# LEDs.net
KiCad netlist of a schematic drawn in EAGLE
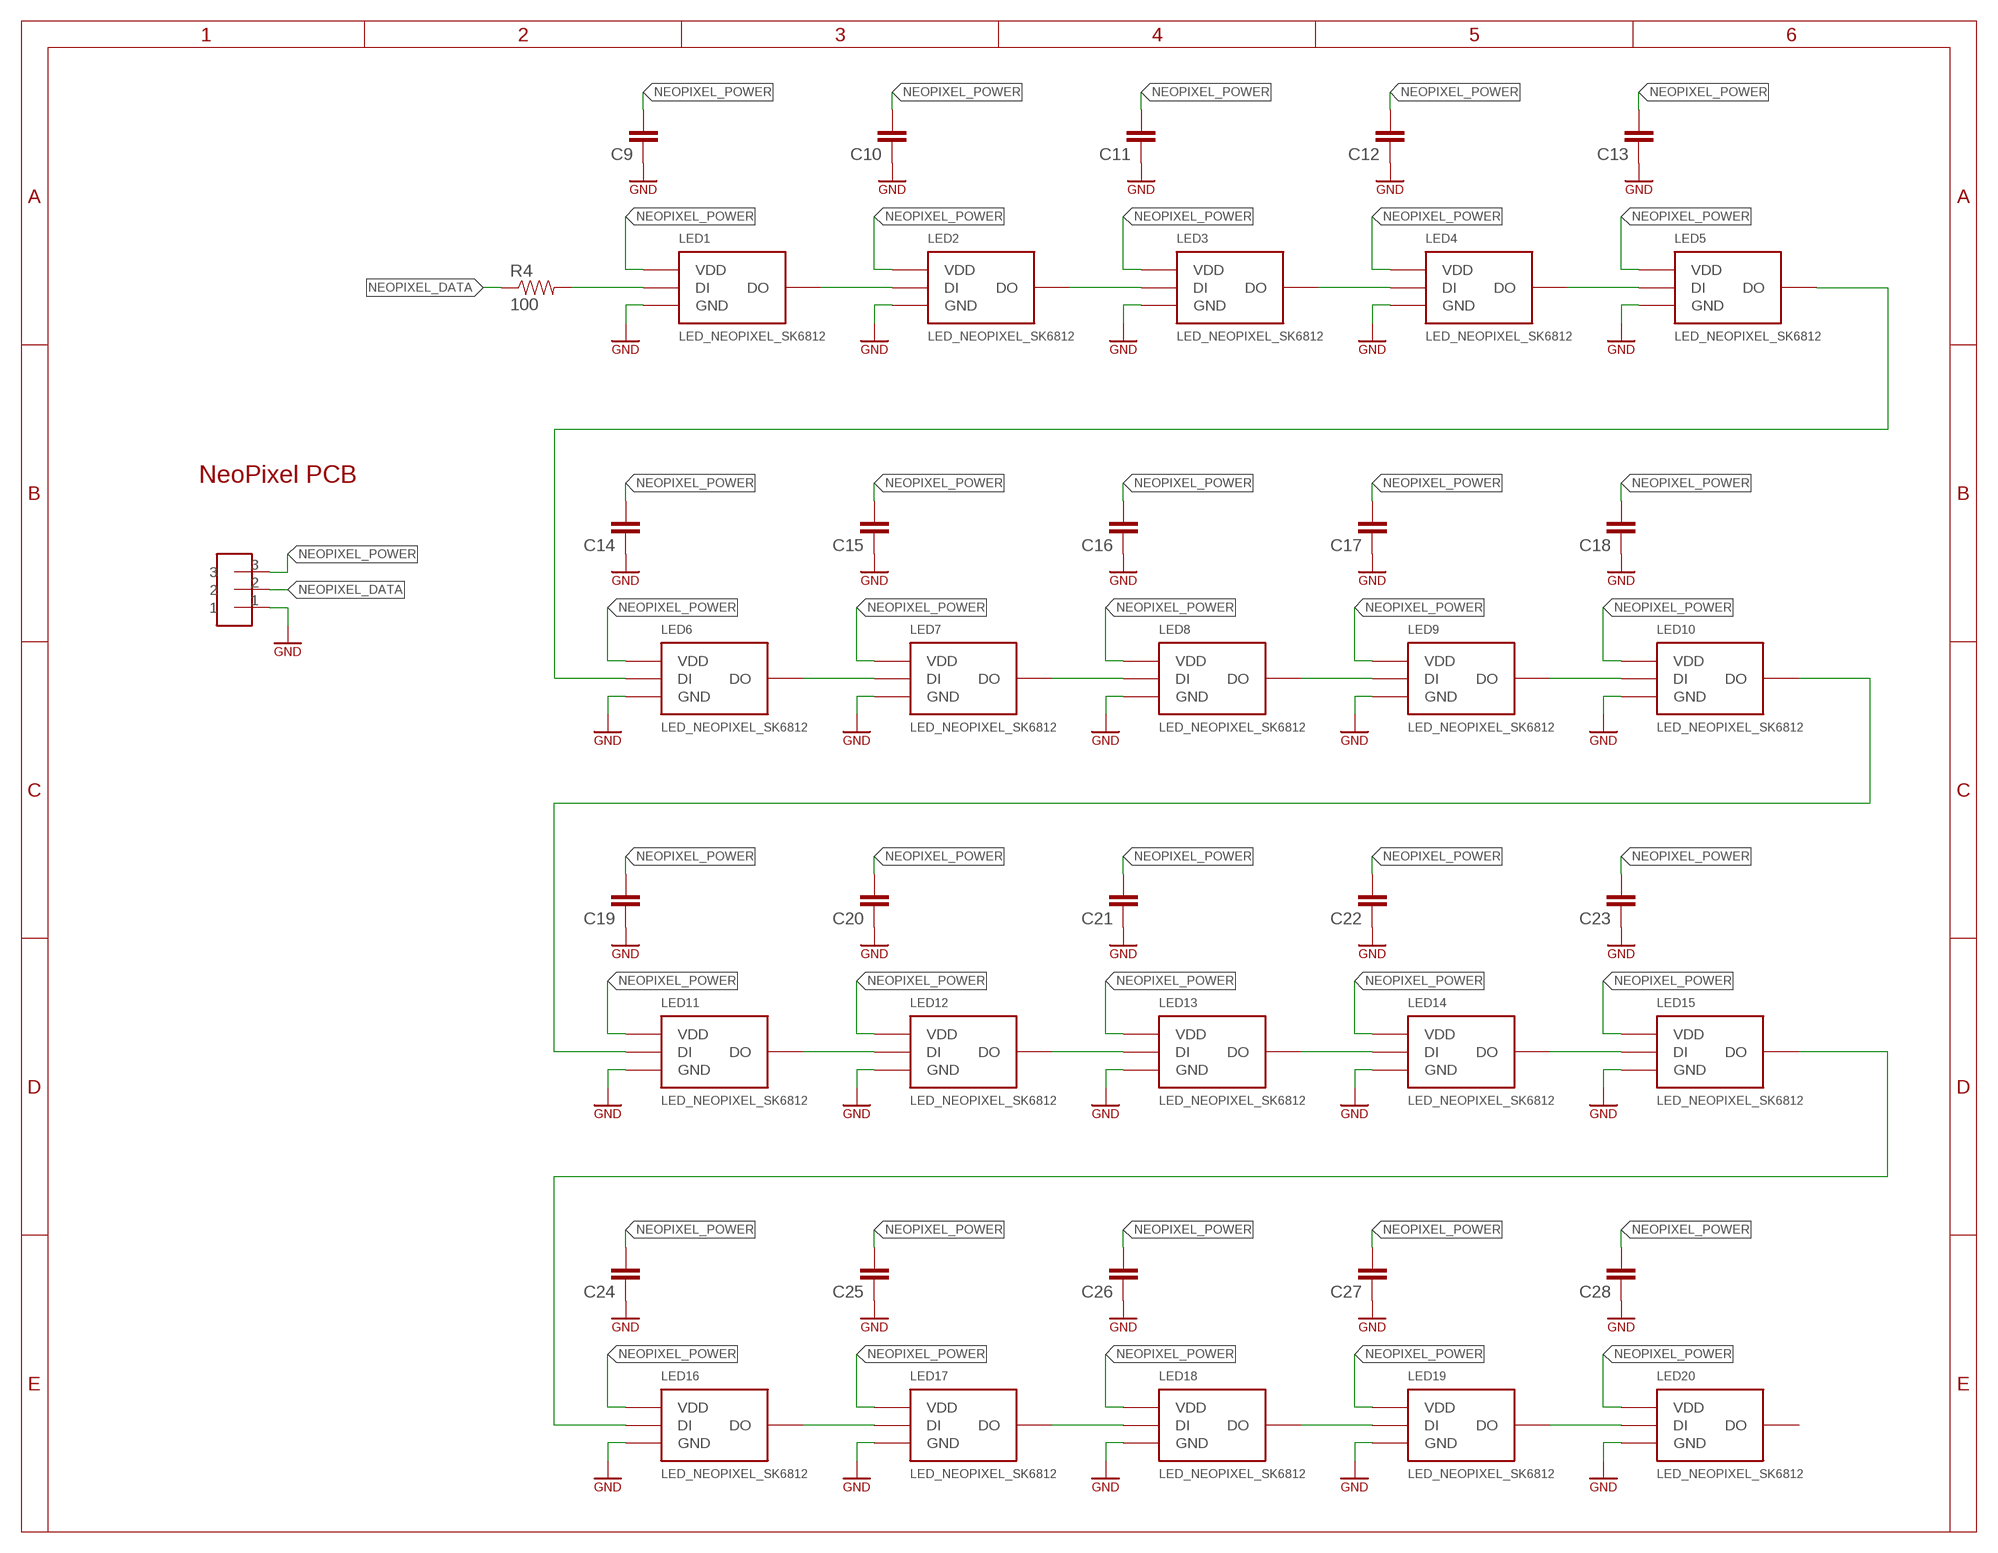
[diagram p0: schematic, sheet 1]

(export (version "E")
  (design (tool "Eeschema 10.0.6"))
  (components
    (comp (ref "C9")
      (value "COMPONENT_CAP-0805")
      (footprint "eagle-import:0805")
      (libsource (lib "eagle-import") (part "COMPONENT_CAP-0805"))
    )
    (comp (ref "C10")
      (value "COMPONENT_CAP-0805")
      (footprint "eagle-import:0805")
      (libsource (lib "eagle-import") (part "COMPONENT_CAP-0805"))
    )
    (comp (ref "C11")
      (value "COMPONENT_CAP-0805")
      (footprint "eagle-import:0805")
      (libsource (lib "eagle-import") (part "COMPONENT_CAP-0805"))
    )
    (comp (ref "C12")
      (value "COMPONENT_CAP-0805")
      (footprint "eagle-import:0805")
      (libsource (lib "eagle-import") (part "COMPONENT_CAP-0805"))
    )
    (comp (ref "C13")
      (value "COMPONENT_CAP-0805")
      (footprint "eagle-import:0805")
      (libsource (lib "eagle-import") (part "COMPONENT_CAP-0805"))
    )
    (comp (ref "C14")
      (value "COMPONENT_CAP-0805")
      (footprint "eagle-import:0805")
      (libsource (lib "eagle-import") (part "COMPONENT_CAP-0805"))
    )
    (comp (ref "C15")
      (value "COMPONENT_CAP-0805")
      (footprint "eagle-import:0805")
      (libsource (lib "eagle-import") (part "COMPONENT_CAP-0805"))
    )
    (comp (ref "C16")
      (value "COMPONENT_CAP-0805")
      (footprint "eagle-import:0805")
      (libsource (lib "eagle-import") (part "COMPONENT_CAP-0805"))
    )
    (comp (ref "C17")
      (value "COMPONENT_CAP-0805")
      (footprint "eagle-import:0805")
      (libsource (lib "eagle-import") (part "COMPONENT_CAP-0805"))
    )
    (comp (ref "C18")
      (value "COMPONENT_CAP-0805")
      (footprint "eagle-import:0805")
      (libsource (lib "eagle-import") (part "COMPONENT_CAP-0805"))
    )
    (comp (ref "C19")
      (value "COMPONENT_CAP-0805")
      (footprint "eagle-import:0805")
      (libsource (lib "eagle-import") (part "COMPONENT_CAP-0805"))
    )
    (comp (ref "C20")
      (value "COMPONENT_CAP-0805")
      (footprint "eagle-import:0805")
      (libsource (lib "eagle-import") (part "COMPONENT_CAP-0805"))
    )
    (comp (ref "C21")
      (value "COMPONENT_CAP-0805")
      (footprint "eagle-import:0805")
      (libsource (lib "eagle-import") (part "COMPONENT_CAP-0805"))
    )
    (comp (ref "C22")
      (value "COMPONENT_CAP-0805")
      (footprint "eagle-import:0805")
      (libsource (lib "eagle-import") (part "COMPONENT_CAP-0805"))
    )
    (comp (ref "C23")
      (value "COMPONENT_CAP-0805")
      (footprint "eagle-import:0805")
      (libsource (lib "eagle-import") (part "COMPONENT_CAP-0805"))
    )
    (comp (ref "C24")
      (value "COMPONENT_CAP-0805")
      (footprint "eagle-import:0805")
      (libsource (lib "eagle-import") (part "COMPONENT_CAP-0805"))
    )
    (comp (ref "C25")
      (value "COMPONENT_CAP-0805")
      (footprint "eagle-import:0805")
      (libsource (lib "eagle-import") (part "COMPONENT_CAP-0805"))
    )
    (comp (ref "C26")
      (value "COMPONENT_CAP-0805")
      (footprint "eagle-import:0805")
      (libsource (lib "eagle-import") (part "COMPONENT_CAP-0805"))
    )
    (comp (ref "C27")
      (value "COMPONENT_CAP-0805")
      (footprint "eagle-import:0805")
      (libsource (lib "eagle-import") (part "COMPONENT_CAP-0805"))
    )
    (comp (ref "C28")
      (value "COMPONENT_CAP-0805")
      (footprint "eagle-import:0805")
      (libsource (lib "eagle-import") (part "COMPONENT_CAP-0805"))
    )
    (comp (ref "LED1")
      (value "LED_NEOPIXEL_SK6812")
      (footprint "eagle-import:SK6812")
      (libsource (lib "eagle-import") (part "LED_NEOPIXEL_SK6812"))
    )
    (comp (ref "LED2")
      (value "LED_NEOPIXEL_SK6812")
      (footprint "eagle-import:SK6812")
      (libsource (lib "eagle-import") (part "LED_NEOPIXEL_SK6812"))
    )
    (comp (ref "LED3")
      (value "LED_NEOPIXEL_SK6812")
      (footprint "eagle-import:SK6812")
      (libsource (lib "eagle-import") (part "LED_NEOPIXEL_SK6812"))
    )
    (comp (ref "LED4")
      (value "LED_NEOPIXEL_SK6812")
      (footprint "eagle-import:SK6812")
      (libsource (lib "eagle-import") (part "LED_NEOPIXEL_SK6812"))
    )
    (comp (ref "LED5")
      (value "LED_NEOPIXEL_SK6812")
      (footprint "eagle-import:SK6812")
      (libsource (lib "eagle-import") (part "LED_NEOPIXEL_SK6812"))
    )
    (comp (ref "LED6")
      (value "LED_NEOPIXEL_SK6812")
      (footprint "eagle-import:SK6812")
      (libsource (lib "eagle-import") (part "LED_NEOPIXEL_SK6812"))
    )
    (comp (ref "LED7")
      (value "LED_NEOPIXEL_SK6812")
      (footprint "eagle-import:SK6812")
      (libsource (lib "eagle-import") (part "LED_NEOPIXEL_SK6812"))
    )
    (comp (ref "LED8")
      (value "LED_NEOPIXEL_SK6812")
      (footprint "eagle-import:SK6812")
      (libsource (lib "eagle-import") (part "LED_NEOPIXEL_SK6812"))
    )
    (comp (ref "LED9")
      (value "LED_NEOPIXEL_SK6812")
      (footprint "eagle-import:SK6812")
      (libsource (lib "eagle-import") (part "LED_NEOPIXEL_SK6812"))
    )
    (comp (ref "LED10")
      (value "LED_NEOPIXEL_SK6812")
      (footprint "eagle-import:SK6812")
      (libsource (lib "eagle-import") (part "LED_NEOPIXEL_SK6812"))
    )
    (comp (ref "LED11")
      (value "LED_NEOPIXEL_SK6812")
      (footprint "eagle-import:SK6812")
      (libsource (lib "eagle-import") (part "LED_NEOPIXEL_SK6812"))
    )
    (comp (ref "LED12")
      (value "LED_NEOPIXEL_SK6812")
      (footprint "eagle-import:SK6812")
      (libsource (lib "eagle-import") (part "LED_NEOPIXEL_SK6812"))
    )
    (comp (ref "LED13")
      (value "LED_NEOPIXEL_SK6812")
      (footprint "eagle-import:SK6812")
      (libsource (lib "eagle-import") (part "LED_NEOPIXEL_SK6812"))
    )
    (comp (ref "LED14")
      (value "LED_NEOPIXEL_SK6812")
      (footprint "eagle-import:SK6812")
      (libsource (lib "eagle-import") (part "LED_NEOPIXEL_SK6812"))
    )
    (comp (ref "LED15")
      (value "LED_NEOPIXEL_SK6812")
      (footprint "eagle-import:SK6812")
      (libsource (lib "eagle-import") (part "LED_NEOPIXEL_SK6812"))
    )
    (comp (ref "LED16")
      (value "LED_NEOPIXEL_SK6812")
      (footprint "eagle-import:SK6812")
      (libsource (lib "eagle-import") (part "LED_NEOPIXEL_SK6812"))
    )
    (comp (ref "LED17")
      (value "LED_NEOPIXEL_SK6812")
      (footprint "eagle-import:SK6812")
      (libsource (lib "eagle-import") (part "LED_NEOPIXEL_SK6812"))
    )
    (comp (ref "LED18")
      (value "LED_NEOPIXEL_SK6812")
      (footprint "eagle-import:SK6812")
      (libsource (lib "eagle-import") (part "LED_NEOPIXEL_SK6812"))
    )
    (comp (ref "LED19")
      (value "LED_NEOPIXEL_SK6812")
      (footprint "eagle-import:SK6812")
      (libsource (lib "eagle-import") (part "LED_NEOPIXEL_SK6812"))
    )
    (comp (ref "LED20")
      (value "LED_NEOPIXEL_SK6812")
      (footprint "eagle-import:SK6812")
      (libsource (lib "eagle-import") (part "LED_NEOPIXEL_SK6812"))
    )
    (comp (ref "R4")
      (value "100")
      (footprint "eagle-import:0805")
      (libsource (lib "eagle-import") (part "COMPONENT_RESISTOR-0805"))
    )
    (comp (ref "U$2")
      (value "HEADER-3-HORIZONTAL")
      (footprint "eagle-import:HEADER-3-HORIZONTAL")
      (libsource (lib "eagle-import") (part "HEADER-3-HORIZONTAL"))
    )
  )
  (nets
    (net (code "1") (name "NEOPIXEL_DATA") (class "Default")
      (node (ref "R4") (pin "1") (pinfunction "1_1") (pintype "passive"))
      (node (ref "U$2") (pin "2") (pinfunction "2_2") (pintype "bidirectional"))
    )
    (net (code "2") (name "NEOPIXEL_POWER") (class "Default")
      (node (ref "C10") (pin "2") (pinfunction "2_2") (pintype "passive"))
      (node (ref "C11") (pin "2") (pinfunction "2_2") (pintype "passive"))
      (node (ref "C12") (pin "2") (pinfunction "2_2") (pintype "passive"))
      (node (ref "C13") (pin "2") (pinfunction "2_2") (pintype "passive"))
      (node (ref "C14") (pin "2") (pinfunction "2_2") (pintype "passive"))
      (node (ref "C15") (pin "2") (pinfunction "2_2") (pintype "passive"))
      (node (ref "C16") (pin "2") (pinfunction "2_2") (pintype "passive"))
      (node (ref "C17") (pin "2") (pinfunction "2_2") (pintype "passive"))
      (node (ref "C18") (pin "2") (pinfunction "2_2") (pintype "passive"))
      (node (ref "C19") (pin "2") (pinfunction "2_2") (pintype "passive"))
      (node (ref "C20") (pin "2") (pinfunction "2_2") (pintype "passive"))
      (node (ref "C21") (pin "2") (pinfunction "2_2") (pintype "passive"))
      (node (ref "C22") (pin "2") (pinfunction "2_2") (pintype "passive"))
      (node (ref "C23") (pin "2") (pinfunction "2_2") (pintype "passive"))
      (node (ref "C24") (pin "2") (pinfunction "2_2") (pintype "passive"))
      (node (ref "C25") (pin "2") (pinfunction "2_2") (pintype "passive"))
      (node (ref "C26") (pin "2") (pinfunction "2_2") (pintype "passive"))
      (node (ref "C27") (pin "2") (pinfunction "2_2") (pintype "passive"))
      (node (ref "C28") (pin "2") (pinfunction "2_2") (pintype "passive"))
      (node (ref "C9") (pin "2") (pinfunction "2_2") (pintype "passive"))
      (node (ref "LED1") (pin "1-VDD") (pinfunction "VDD_1-VDD") (pintype "power_in"))
      (node (ref "LED10") (pin "1-VDD") (pinfunction "VDD_1-VDD") (pintype "power_in"))
      (node (ref "LED11") (pin "1-VDD") (pinfunction "VDD_1-VDD") (pintype "power_in"))
      (node (ref "LED12") (pin "1-VDD") (pinfunction "VDD_1-VDD") (pintype "power_in"))
      (node (ref "LED13") (pin "1-VDD") (pinfunction "VDD_1-VDD") (pintype "power_in"))
      (node (ref "LED14") (pin "1-VDD") (pinfunction "VDD_1-VDD") (pintype "power_in"))
      (node (ref "LED15") (pin "1-VDD") (pinfunction "VDD_1-VDD") (pintype "power_in"))
      (node (ref "LED16") (pin "1-VDD") (pinfunction "VDD_1-VDD") (pintype "power_in"))
      (node (ref "LED17") (pin "1-VDD") (pinfunction "VDD_1-VDD") (pintype "power_in"))
      (node (ref "LED18") (pin "1-VDD") (pinfunction "VDD_1-VDD") (pintype "power_in"))
      (node (ref "LED19") (pin "1-VDD") (pinfunction "VDD_1-VDD") (pintype "power_in"))
      (node (ref "LED2") (pin "1-VDD") (pinfunction "VDD_1-VDD") (pintype "power_in"))
      (node (ref "LED20") (pin "1-VDD") (pinfunction "VDD_1-VDD") (pintype "power_in"))
      (node (ref "LED3") (pin "1-VDD") (pinfunction "VDD_1-VDD") (pintype "power_in"))
      (node (ref "LED4") (pin "1-VDD") (pinfunction "VDD_1-VDD") (pintype "power_in"))
      (node (ref "LED5") (pin "1-VDD") (pinfunction "VDD_1-VDD") (pintype "power_in"))
      (node (ref "LED6") (pin "1-VDD") (pinfunction "VDD_1-VDD") (pintype "power_in"))
      (node (ref "LED7") (pin "1-VDD") (pinfunction "VDD_1-VDD") (pintype "power_in"))
      (node (ref "LED8") (pin "1-VDD") (pinfunction "VDD_1-VDD") (pintype "power_in"))
      (node (ref "LED9") (pin "1-VDD") (pinfunction "VDD_1-VDD") (pintype "power_in"))
      (node (ref "U$2") (pin "3") (pinfunction "3_3") (pintype "bidirectional"))
    )
    (net (code "3") (name "Net-(LED1-DI)") (class "Default")
      (node (ref "LED1") (pin "4-DIN") (pinfunction "DI_4-DIN") (pintype "input"))
      (node (ref "R4") (pin "2") (pinfunction "2_2") (pintype "passive"))
    )
    (net (code "4") (name "Net-(LED1-DO)") (class "Default")
      (node (ref "LED1") (pin "2-DOUT") (pinfunction "DO_2-DOUT") (pintype "output"))
      (node (ref "LED2") (pin "4-DIN") (pinfunction "DI_4-DIN") (pintype "input"))
    )
    (net (code "5") (name "Net-(LED2-DO)") (class "Default")
      (node (ref "LED2") (pin "2-DOUT") (pinfunction "DO_2-DOUT") (pintype "output"))
      (node (ref "LED3") (pin "4-DIN") (pinfunction "DI_4-DIN") (pintype "input"))
    )
    (net (code "6") (name "Net-(LED3-DO)") (class "Default")
      (node (ref "LED3") (pin "2-DOUT") (pinfunction "DO_2-DOUT") (pintype "output"))
      (node (ref "LED4") (pin "4-DIN") (pinfunction "DI_4-DIN") (pintype "input"))
    )
    (net (code "7") (name "Net-(LED4-DO)") (class "Default")
      (node (ref "LED4") (pin "2-DOUT") (pinfunction "DO_2-DOUT") (pintype "output"))
      (node (ref "LED5") (pin "4-DIN") (pinfunction "DI_4-DIN") (pintype "input"))
    )
    (net (code "8") (name "Net-(LED5-DO)") (class "Default")
      (node (ref "LED5") (pin "2-DOUT") (pinfunction "DO_2-DOUT") (pintype "output"))
      (node (ref "LED6") (pin "4-DIN") (pinfunction "DI_4-DIN") (pintype "input"))
    )
    (net (code "9") (name "Net-(LED6-DO)") (class "Default")
      (node (ref "LED6") (pin "2-DOUT") (pinfunction "DO_2-DOUT") (pintype "output"))
      (node (ref "LED7") (pin "4-DIN") (pinfunction "DI_4-DIN") (pintype "input"))
    )
    (net (code "10") (name "Net-(LED7-DO)") (class "Default")
      (node (ref "LED7") (pin "2-DOUT") (pinfunction "DO_2-DOUT") (pintype "output"))
      (node (ref "LED8") (pin "4-DIN") (pinfunction "DI_4-DIN") (pintype "input"))
    )
    (net (code "11") (name "Net-(LED8-DO)") (class "Default")
      (node (ref "LED8") (pin "2-DOUT") (pinfunction "DO_2-DOUT") (pintype "output"))
      (node (ref "LED9") (pin "4-DIN") (pinfunction "DI_4-DIN") (pintype "input"))
    )
    (net (code "12") (name "Net-(LED10-DI)") (class "Default")
      (node (ref "LED10") (pin "4-DIN") (pinfunction "DI_4-DIN") (pintype "input"))
      (node (ref "LED9") (pin "2-DOUT") (pinfunction "DO_2-DOUT") (pintype "output"))
    )
    (net (code "13") (name "Net-(LED10-DO)") (class "Default")
      (node (ref "LED10") (pin "2-DOUT") (pinfunction "DO_2-DOUT") (pintype "output"))
      (node (ref "LED11") (pin "4-DIN") (pinfunction "DI_4-DIN") (pintype "input"))
    )
    (net (code "14") (name "Net-(LED11-DO)") (class "Default")
      (node (ref "LED11") (pin "2-DOUT") (pinfunction "DO_2-DOUT") (pintype "output"))
      (node (ref "LED12") (pin "4-DIN") (pinfunction "DI_4-DIN") (pintype "input"))
    )
    (net (code "15") (name "Net-(LED12-DO)") (class "Default")
      (node (ref "LED12") (pin "2-DOUT") (pinfunction "DO_2-DOUT") (pintype "output"))
      (node (ref "LED13") (pin "4-DIN") (pinfunction "DI_4-DIN") (pintype "input"))
    )
    (net (code "16") (name "Net-(LED13-DO)") (class "Default")
      (node (ref "LED13") (pin "2-DOUT") (pinfunction "DO_2-DOUT") (pintype "output"))
      (node (ref "LED14") (pin "4-DIN") (pinfunction "DI_4-DIN") (pintype "input"))
    )
    (net (code "17") (name "Net-(LED14-DO)") (class "Default")
      (node (ref "LED14") (pin "2-DOUT") (pinfunction "DO_2-DOUT") (pintype "output"))
      (node (ref "LED15") (pin "4-DIN") (pinfunction "DI_4-DIN") (pintype "input"))
    )
    (net (code "18") (name "Net-(LED15-DO)") (class "Default")
      (node (ref "LED15") (pin "2-DOUT") (pinfunction "DO_2-DOUT") (pintype "output"))
      (node (ref "LED16") (pin "4-DIN") (pinfunction "DI_4-DIN") (pintype "input"))
    )
    (net (code "19") (name "Net-(LED16-DO)") (class "Default")
      (node (ref "LED16") (pin "2-DOUT") (pinfunction "DO_2-DOUT") (pintype "output"))
      (node (ref "LED17") (pin "4-DIN") (pinfunction "DI_4-DIN") (pintype "input"))
    )
    (net (code "20") (name "Net-(LED17-DO)") (class "Default")
      (node (ref "LED17") (pin "2-DOUT") (pinfunction "DO_2-DOUT") (pintype "output"))
      (node (ref "LED18") (pin "4-DIN") (pinfunction "DI_4-DIN") (pintype "input"))
    )
    (net (code "21") (name "Net-(LED18-DO)") (class "Default")
      (node (ref "LED18") (pin "2-DOUT") (pinfunction "DO_2-DOUT") (pintype "output"))
      (node (ref "LED19") (pin "4-DIN") (pinfunction "DI_4-DIN") (pintype "input"))
    )
    (net (code "22") (name "Net-(LED19-DO)") (class "Default")
      (node (ref "LED19") (pin "2-DOUT") (pinfunction "DO_2-DOUT") (pintype "output"))
      (node (ref "LED20") (pin "4-DIN") (pinfunction "DI_4-DIN") (pintype "input"))
    )
    (net (code "23") (name "SYMBOL_GND") (class "Default")
      (node (ref "C10") (pin "1") (pinfunction "1_1") (pintype "passive"))
      (node (ref "C11") (pin "1") (pinfunction "1_1") (pintype "passive"))
      (node (ref "C12") (pin "1") (pinfunction "1_1") (pintype "passive"))
      (node (ref "C13") (pin "1") (pinfunction "1_1") (pintype "passive"))
      (node (ref "C14") (pin "1") (pinfunction "1_1") (pintype "passive"))
      (node (ref "C15") (pin "1") (pinfunction "1_1") (pintype "passive"))
      (node (ref "C16") (pin "1") (pinfunction "1_1") (pintype "passive"))
      (node (ref "C17") (pin "1") (pinfunction "1_1") (pintype "passive"))
      (node (ref "C18") (pin "1") (pinfunction "1_1") (pintype "passive"))
      (node (ref "C19") (pin "1") (pinfunction "1_1") (pintype "passive"))
      (node (ref "C20") (pin "1") (pinfunction "1_1") (pintype "passive"))
      (node (ref "C21") (pin "1") (pinfunction "1_1") (pintype "passive"))
      (node (ref "C22") (pin "1") (pinfunction "1_1") (pintype "passive"))
      (node (ref "C23") (pin "1") (pinfunction "1_1") (pintype "passive"))
      (node (ref "C24") (pin "1") (pinfunction "1_1") (pintype "passive"))
      (node (ref "C25") (pin "1") (pinfunction "1_1") (pintype "passive"))
      (node (ref "C26") (pin "1") (pinfunction "1_1") (pintype "passive"))
      (node (ref "C27") (pin "1") (pinfunction "1_1") (pintype "passive"))
      (node (ref "C28") (pin "1") (pinfunction "1_1") (pintype "passive"))
      (node (ref "C9") (pin "1") (pinfunction "1_1") (pintype "passive"))
      (node (ref "LED1") (pin "3-GND") (pinfunction "GND_3-GND") (pintype "power_in"))
      (node (ref "LED10") (pin "3-GND") (pinfunction "GND_3-GND") (pintype "power_in"))
      (node (ref "LED11") (pin "3-GND") (pinfunction "GND_3-GND") (pintype "power_in"))
      (node (ref "LED12") (pin "3-GND") (pinfunction "GND_3-GND") (pintype "power_in"))
      (node (ref "LED13") (pin "3-GND") (pinfunction "GND_3-GND") (pintype "power_in"))
      (node (ref "LED14") (pin "3-GND") (pinfunction "GND_3-GND") (pintype "power_in"))
      (node (ref "LED15") (pin "3-GND") (pinfunction "GND_3-GND") (pintype "power_in"))
      (node (ref "LED16") (pin "3-GND") (pinfunction "GND_3-GND") (pintype "power_in"))
      (node (ref "LED17") (pin "3-GND") (pinfunction "GND_3-GND") (pintype "power_in"))
      (node (ref "LED18") (pin "3-GND") (pinfunction "GND_3-GND") (pintype "power_in"))
      (node (ref "LED19") (pin "3-GND") (pinfunction "GND_3-GND") (pintype "power_in"))
      (node (ref "LED2") (pin "3-GND") (pinfunction "GND_3-GND") (pintype "power_in"))
      (node (ref "LED20") (pin "3-GND") (pinfunction "GND_3-GND") (pintype "power_in"))
      (node (ref "LED3") (pin "3-GND") (pinfunction "GND_3-GND") (pintype "power_in"))
      (node (ref "LED4") (pin "3-GND") (pinfunction "GND_3-GND") (pintype "power_in"))
      (node (ref "LED5") (pin "3-GND") (pinfunction "GND_3-GND") (pintype "power_in"))
      (node (ref "LED6") (pin "3-GND") (pinfunction "GND_3-GND") (pintype "power_in"))
      (node (ref "LED7") (pin "3-GND") (pinfunction "GND_3-GND") (pintype "power_in"))
      (node (ref "LED8") (pin "3-GND") (pinfunction "GND_3-GND") (pintype "power_in"))
      (node (ref "LED9") (pin "3-GND") (pinfunction "GND_3-GND") (pintype "power_in"))
      (node (ref "U$2") (pin "1") (pinfunction "1_1") (pintype "bidirectional"))
    )
    (net (code "24") (name "unconnected-(LED20-DO-Pad2-DOUT)") (class "Default")
      (node (ref "LED20") (pin "2-DOUT") (pinfunction "DO_2-DOUT") (pintype "output"))
    )
  )
)
